# my_board3.net
KiCad netlist of a schematic drawn in EAGLE
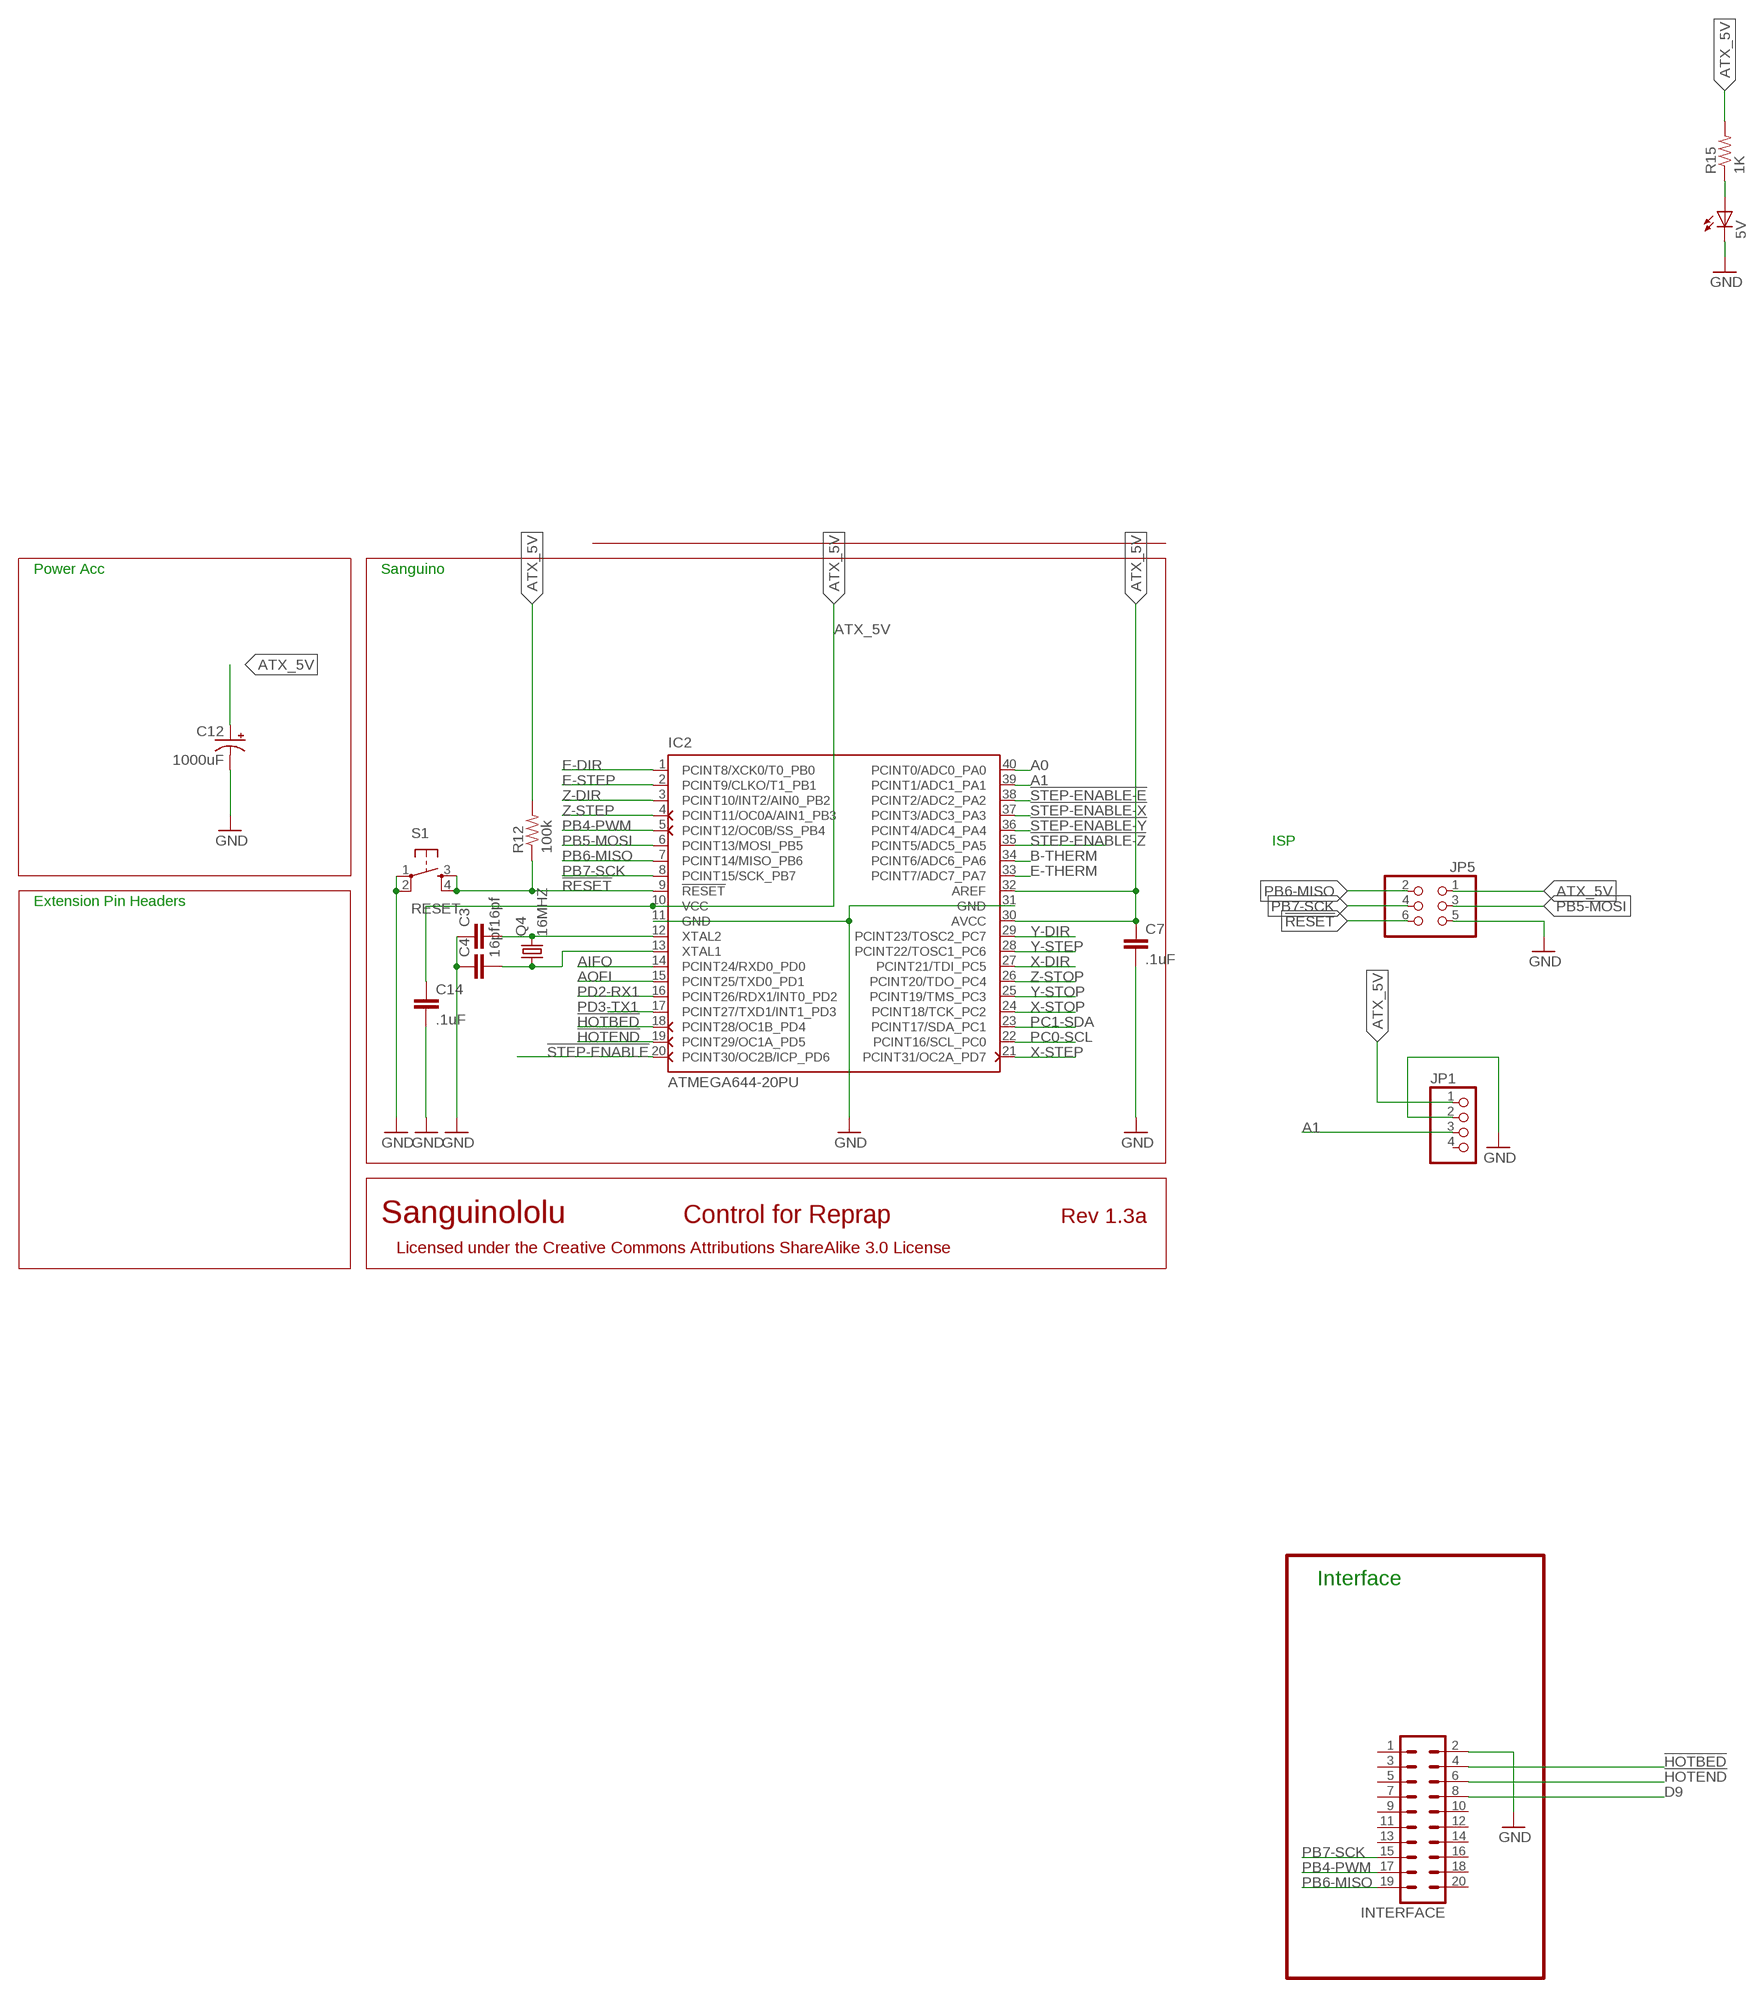
[diagram p0: schematic, sheet 1, part 1 of 2]
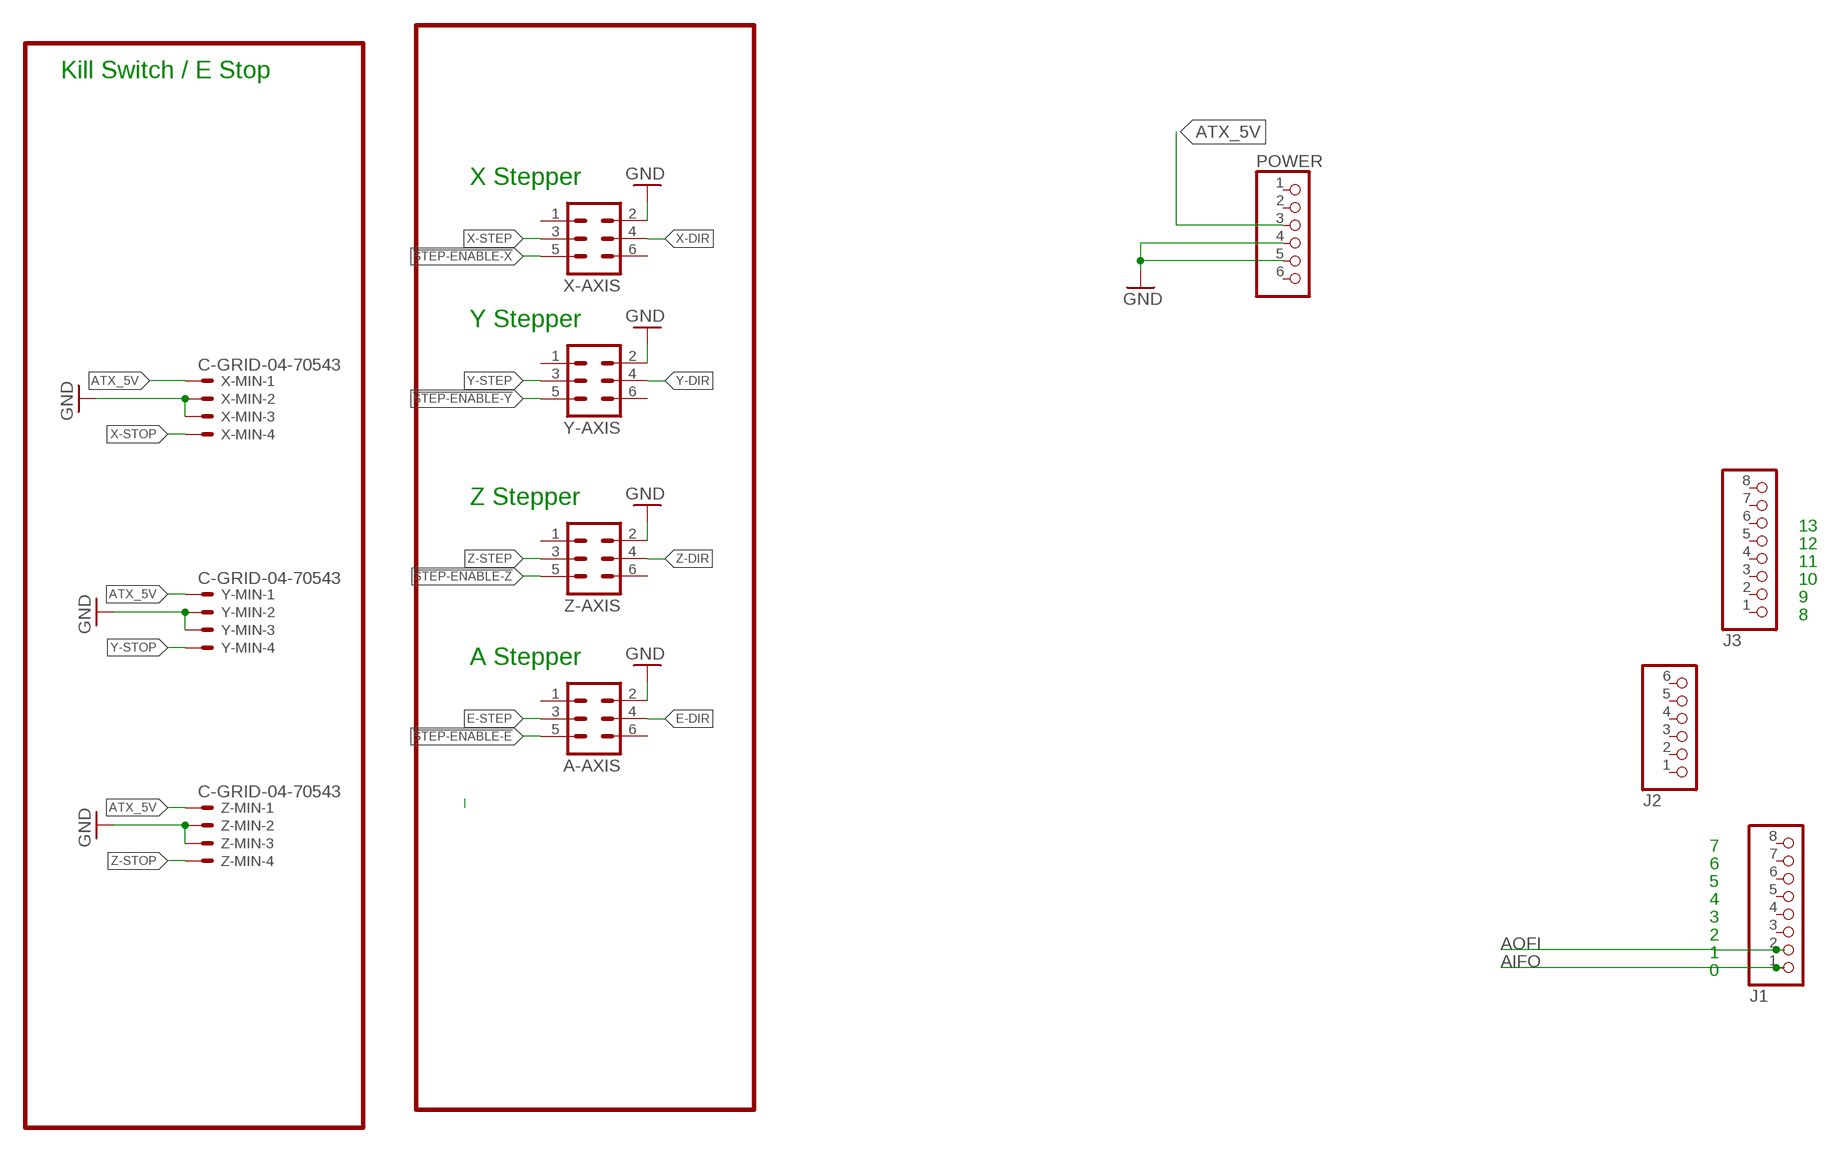
[diagram p1: schematic, sheet 1, part 2 of 2]

(export (version "E")
  (design (tool "Eeschema 10.0.6"))
  (components
    (comp (ref "5V")
      (value "LED0805")
      (footprint "eagle-import:LED-0805")
      (libsource (lib "eagle-import") (part "LED0805"))
    )
    (comp (ref "A-AXIS")
      (value "ML6")
      (footprint "eagle-import:ML6")
      (libsource (lib "eagle-import") (part "ML6"))
    )
    (comp (ref "C3")
      (value "16pf")
      (footprint "eagle-import:0805")
      (libsource (lib "eagle-import") (part "CAP0805"))
    )
    (comp (ref "C4")
      (value "16pf")
      (footprint "eagle-import:0805")
      (libsource (lib "eagle-import") (part "CAP0805"))
    )
    (comp (ref "C7")
      (value ".1uF")
      (footprint "eagle-import:0805")
      (libsource (lib "eagle-import") (part "CAP0805"))
    )
    (comp (ref "C12")
      (value "1000uF")
      (footprint "eagle-import:CPOL-RADIAL-1000UF-25V")
      (libsource (lib "eagle-import") (part "CAP_POLPTH4"))
    )
    (comp (ref "C14")
      (value ".1uF")
      (footprint "eagle-import:0805")
      (libsource (lib "eagle-import") (part "CAP0805"))
    )
    (comp (ref "IC2")
      (value "ATMEGA644-20PU")
      (footprint "eagle-import:DIL40")
      (libsource (lib "eagle-import") (part "ATMEGA644-PU20"))
    )
    (comp (ref "INTERFACE")
      (value "ML20")
      (footprint "eagle-import:ML20")
      (libsource (lib "eagle-import") (part "ML20"))
    )
    (comp (ref "J1")
      (value "PINHD-1X8")
      (footprint "eagle-import:1X08")
      (libsource (lib "eagle-import") (part "PINHD-1X8"))
    )
    (comp (ref "J2")
      (value "PINHD-1X6")
      (footprint "eagle-import:1X06")
      (libsource (lib "eagle-import") (part "PINHD-1X6"))
    )
    (comp (ref "J3")
      (value "PINHD-1X8")
      (footprint "eagle-import:1X08")
      (libsource (lib "eagle-import") (part "PINHD-1X8"))
    )
    (comp (ref "JP1")
      (value "PINHD-1X4")
      (footprint "eagle-import:1X04")
      (libsource (lib "eagle-import") (part "PINHD-1X4"))
    )
    (comp (ref "JP5")
      (value "PINHD-2X3")
      (footprint "eagle-import:2X03")
      (libsource (lib "eagle-import") (part "PINHD-2X3"))
    )
    (comp (ref "POWER")
      (value "PINHD-1X6")
      (footprint "eagle-import:1X06")
      (libsource (lib "eagle-import") (part "PINHD-1X6"))
    )
    (comp (ref "Q4")
      (value "16MHZ")
      (footprint "eagle-import:HC49_S")
      (libsource (lib "eagle-import") (part "CRYSTALHC49S"))
    )
    (comp (ref "R12")
      (value "100k")
      (footprint "eagle-import:AXIAL-0.3")
      (libsource (lib "eagle-import") (part "RESISTORPTH1"))
    )
    (comp (ref "R15")
      (value "1K")
      (footprint "eagle-import:0805")
      (libsource (lib "eagle-import") (part "RESISTOR"))
    )
    (comp (ref "S1")
      (value "RESET")
      (footprint "eagle-import:TACTILE-PTH")
      (libsource (lib "eagle-import") (part "TAC_SWITCHPTH"))
    )
    (comp (ref "X-AXIS")
      (value "ML6")
      (footprint "eagle-import:ML6")
      (libsource (lib "eagle-import") (part "ML6"))
    )
    (comp (ref "X-MIN")
      (value "C-GRID-04-70543")
      (footprint "eagle-import:70543-04")
      (libsource (lib "eagle-import") (part "C-GRID-04-70543"))
    )
    (comp (ref "Y-AXIS")
      (value "ML6")
      (footprint "eagle-import:ML6")
      (libsource (lib "eagle-import") (part "ML6"))
    )
    (comp (ref "Y-MIN")
      (value "C-GRID-04-70543")
      (footprint "eagle-import:70543-04")
      (libsource (lib "eagle-import") (part "C-GRID-04-70543"))
    )
    (comp (ref "Z-AXIS")
      (value "ML6")
      (footprint "eagle-import:ML6")
      (libsource (lib "eagle-import") (part "ML6"))
    )
    (comp (ref "Z-MIN")
      (value "C-GRID-04-70543")
      (footprint "eagle-import:70543-04")
      (libsource (lib "eagle-import") (part "C-GRID-04-70543"))
    )
  )
  (nets
    (net (code "1") (name "/A0") (class "Default")
      (node (ref "IC2") (pin "40") (pinfunction "PCINT0/ADC0_PA0_40") (pintype "bidirectional"))
    )
    (net (code "2") (name "/A1") (class "Default")
      (node (ref "IC2") (pin "39") (pinfunction "PCINT1/ADC1_PA1_39") (pintype "bidirectional"))
      (node (ref "JP1") (pin "3") (pinfunction "3_3") (pintype "passive"))
    )
    (net (code "3") (name "/AIFO") (class "Default")
      (node (ref "IC2") (pin "14") (pinfunction "PCINT24/RXD0_PD0_14") (pintype "bidirectional"))
      (node (ref "J1") (pin "1") (pinfunction "1_1") (pintype "passive"))
    )
    (net (code "4") (name "/AOFI") (class "Default")
      (node (ref "IC2") (pin "15") (pinfunction "PCINT25/TXD0_PD1_15") (pintype "bidirectional"))
      (node (ref "J1") (pin "2") (pinfunction "2_2") (pintype "passive"))
    )
    (net (code "5") (name "/B-THERM") (class "Default")
      (node (ref "IC2") (pin "34") (pinfunction "PCINT6/ADC6_PA6_34") (pintype "bidirectional"))
    )
    (net (code "6") (name "/D9") (class "Default")
      (node (ref "INTERFACE") (pin "8") (pinfunction "8_8") (pintype "passive"))
    )
    (net (code "7") (name "/E-THERM") (class "Default")
      (node (ref "IC2") (pin "33") (pinfunction "PCINT7/ADC7_PA7_33") (pintype "bidirectional"))
    )
    (net (code "8") (name "/PB4-PWM") (class "Default")
      (node (ref "IC2") (pin "5") (pinfunction "PCINT12/OC0B/SS_PB4_5") (pintype "bidirectional"))
      (node (ref "INTERFACE") (pin "17") (pinfunction "17_17") (pintype "passive"))
    )
    (net (code "9") (name "/PC0-SCL") (class "Default")
      (node (ref "IC2") (pin "22") (pinfunction "PCINT16/SCL_PC0_22") (pintype "bidirectional"))
    )
    (net (code "10") (name "/PC1-SDA") (class "Default")
      (node (ref "IC2") (pin "23") (pinfunction "PCINT17/SDA_PC1_23") (pintype "bidirectional"))
    )
    (net (code "11") (name "/PD2-RX1") (class "Default")
      (node (ref "IC2") (pin "16") (pinfunction "PCINT26/RDX1/INT0_PD2_16") (pintype "bidirectional"))
    )
    (net (code "12") (name "/PD3-TX1") (class "Default")
      (node (ref "IC2") (pin "17") (pinfunction "PCINT27/TXD1/INT1_PD3_17") (pintype "bidirectional"))
    )
    (net (code "13") (name "/~{HOTBED}") (class "Default")
      (node (ref "IC2") (pin "18") (pinfunction "PCINT28/OC1B_PD4_18") (pintype "bidirectional"))
      (node (ref "INTERFACE") (pin "4") (pinfunction "4_4") (pintype "passive"))
    )
    (net (code "14") (name "/~{HOTEND}") (class "Default")
      (node (ref "IC2") (pin "19") (pinfunction "PCINT29/OC1A_PD5_19") (pintype "bidirectional"))
      (node (ref "INTERFACE") (pin "6") (pinfunction "6_6") (pintype "passive"))
    )
    (net (code "15") (name "/~{RESET}") (class "Default")
      (node (ref "IC2") (pin "9") (pinfunction "~{RESET}_9") (pintype "input"))
      (node (ref "JP5") (pin "6") (pinfunction "6_6") (pintype "passive"))
      (node (ref "R12") (pin "P$1") (pinfunction "1_P$1") (pintype "passive"))
      (node (ref "S1") (pin "3") (pinfunction "3_3") (pintype "passive"))
      (node (ref "S1") (pin "4") (pinfunction "4_4") (pintype "passive"))
    )
    (net (code "16") (name "/~{STEP-ENABLE-E}") (class "Default")
      (node (ref "A-AXIS") (pin "5") (pinfunction "5_5") (pintype "passive"))
      (node (ref "IC2") (pin "38") (pinfunction "PCINT2/ADC2_PA2_38") (pintype "bidirectional"))
    )
    (net (code "17") (name "/~{STEP-ENABLE-X}") (class "Default")
      (node (ref "IC2") (pin "37") (pinfunction "PCINT3/ADC3_PA3_37") (pintype "bidirectional"))
      (node (ref "X-AXIS") (pin "5") (pinfunction "5_5") (pintype "passive"))
    )
    (net (code "18") (name "/~{STEP-ENABLE-Y}") (class "Default")
      (node (ref "IC2") (pin "36") (pinfunction "PCINT4/ADC4_PA4_36") (pintype "bidirectional"))
      (node (ref "Y-AXIS") (pin "5") (pinfunction "5_5") (pintype "passive"))
    )
    (net (code "19") (name "/~{STEP-ENABLE-Z}") (class "Default")
      (node (ref "IC2") (pin "35") (pinfunction "PCINT5/ADC5_PA5_35") (pintype "bidirectional"))
      (node (ref "Z-AXIS") (pin "5") (pinfunction "5_5") (pintype "passive"))
    )
    (net (code "20") (name "/~{STEP-ENABLE}") (class "Default")
      (node (ref "IC2") (pin "20") (pinfunction "PCINT30/OC2B/ICP_PD6_20") (pintype "bidirectional"))
    )
    (net (code "21") (name "ATX_5V") (class "Default")
      (node (ref "C12") (pin "1") (pinfunction "+_1") (pintype "passive"))
      (node (ref "C14") (pin "1") (pinfunction "1_1") (pintype "passive"))
      (node (ref "C7") (pin "1") (pinfunction "1_1") (pintype "passive"))
      (node (ref "IC2") (pin "10") (pinfunction "VCC_10") (pintype "power_in"))
      (node (ref "IC2") (pin "30") (pinfunction "AVCC_30") (pintype "power_in"))
      (node (ref "IC2") (pin "32") (pinfunction "AREF_32") (pintype "passive"))
      (node (ref "JP1") (pin "1") (pinfunction "1_1") (pintype "passive"))
      (node (ref "JP5") (pin "1") (pinfunction "1_1") (pintype "passive"))
      (node (ref "POWER") (pin "3") (pinfunction "3_3") (pintype "passive"))
      (node (ref "R12") (pin "P$2") (pinfunction "2_P$2") (pintype "passive"))
      (node (ref "R15") (pin "2") (pinfunction "2_2") (pintype "passive"))
      (node (ref "X-MIN") (pin "1") (pinfunction "S_1") (pintype "passive"))
      (node (ref "Y-MIN") (pin "1") (pinfunction "S_1") (pintype "passive"))
      (node (ref "Z-MIN") (pin "1") (pinfunction "S_1") (pintype "passive"))
    )
    (net (code "22") (name "E-DIR") (class "Default")
      (node (ref "A-AXIS") (pin "4") (pinfunction "4_4") (pintype "passive"))
      (node (ref "IC2") (pin "1") (pinfunction "PCINT8/XCK0/T0_PB0_1") (pintype "bidirectional"))
    )
    (net (code "23") (name "E-STEP") (class "Default")
      (node (ref "A-AXIS") (pin "3") (pinfunction "3_3") (pintype "passive"))
      (node (ref "IC2") (pin "2") (pinfunction "PCINT9/CLKO/T1_PB1_2") (pintype "bidirectional"))
    )
    (net (code "24") (name "GND") (class "Default")
      (node (ref "5V") (pin "C") (pinfunction "C_C") (pintype "passive"))
      (node (ref "A-AXIS") (pin "2") (pinfunction "2_2") (pintype "passive"))
      (node (ref "C12") (pin "2") (pinfunction "-_2") (pintype "passive"))
      (node (ref "C14") (pin "2") (pinfunction "2_2") (pintype "passive"))
      (node (ref "C3") (pin "1") (pinfunction "1_1") (pintype "passive"))
      (node (ref "C4") (pin "1") (pinfunction "1_1") (pintype "passive"))
      (node (ref "C7") (pin "2") (pinfunction "2_2") (pintype "passive"))
      (node (ref "IC2") (pin "11") (pinfunction "GND_11") (pintype "power_in"))
      (node (ref "IC2") (pin "31") (pinfunction "GND_31") (pintype "power_in"))
      (node (ref "INTERFACE") (pin "2") (pinfunction "2_2") (pintype "passive"))
      (node (ref "JP1") (pin "2") (pinfunction "2_2") (pintype "passive"))
      (node (ref "JP5") (pin "5") (pinfunction "5_5") (pintype "passive"))
      (node (ref "POWER") (pin "4") (pinfunction "4_4") (pintype "passive"))
      (node (ref "POWER") (pin "5") (pinfunction "5_5") (pintype "passive"))
      (node (ref "S1") (pin "1") (pinfunction "1_1") (pintype "passive"))
      (node (ref "S1") (pin "2") (pinfunction "2_2") (pintype "passive"))
      (node (ref "X-AXIS") (pin "2") (pinfunction "2_2") (pintype "passive"))
      (node (ref "X-MIN") (pin "2") (pinfunction "S_2") (pintype "passive"))
      (node (ref "X-MIN") (pin "3") (pinfunction "S_3") (pintype "passive"))
      (node (ref "Y-AXIS") (pin "2") (pinfunction "2_2") (pintype "passive"))
      (node (ref "Y-MIN") (pin "2") (pinfunction "S_2") (pintype "passive"))
      (node (ref "Y-MIN") (pin "3") (pinfunction "S_3") (pintype "passive"))
      (node (ref "Z-AXIS") (pin "2") (pinfunction "2_2") (pintype "passive"))
      (node (ref "Z-MIN") (pin "2") (pinfunction "S_2") (pintype "passive"))
      (node (ref "Z-MIN") (pin "3") (pinfunction "S_3") (pintype "passive"))
    )
    (net (code "25") (name "Net-(5V-PadA)") (class "Default")
      (node (ref "5V") (pin "A") (pinfunction "A_A") (pintype "passive"))
      (node (ref "R15") (pin "1") (pinfunction "1_1") (pintype "passive"))
    )
    (net (code "26") (name "Net-(IC2-XTAL1)") (class "Default")
      (node (ref "C4") (pin "2") (pinfunction "2_2") (pintype "passive"))
      (node (ref "IC2") (pin "13") (pinfunction "XTAL1_13") (pintype "input"))
      (node (ref "Q4") (pin "1") (pinfunction "1_1") (pintype "passive"))
    )
    (net (code "27") (name "Net-(IC2-XTAL2)") (class "Default")
      (node (ref "C3") (pin "2") (pinfunction "2_2") (pintype "passive"))
      (node (ref "IC2") (pin "12") (pinfunction "XTAL2_12") (pintype "output"))
      (node (ref "Q4") (pin "2") (pinfunction "2_2") (pintype "passive"))
    )
    (net (code "28") (name "PB5-MOSI") (class "Default")
      (node (ref "IC2") (pin "6") (pinfunction "PCINT13/MOSI_PB5_6") (pintype "bidirectional"))
      (node (ref "JP5") (pin "3") (pinfunction "3_3") (pintype "passive"))
    )
    (net (code "29") (name "PB6-MISO") (class "Default")
      (node (ref "IC2") (pin "7") (pinfunction "PCINT14/MISO_PB6_7") (pintype "bidirectional"))
      (node (ref "INTERFACE") (pin "19") (pinfunction "19_19") (pintype "passive"))
      (node (ref "JP5") (pin "2") (pinfunction "2_2") (pintype "passive"))
    )
    (net (code "30") (name "PB7-SCK") (class "Default")
      (node (ref "IC2") (pin "8") (pinfunction "PCINT15/SCK_PB7_8") (pintype "bidirectional"))
      (node (ref "INTERFACE") (pin "15") (pinfunction "15_15") (pintype "passive"))
      (node (ref "JP5") (pin "4") (pinfunction "4_4") (pintype "passive"))
    )
    (net (code "31") (name "X-DIR") (class "Default")
      (node (ref "IC2") (pin "27") (pinfunction "PCINT21/TDI_PC5_27") (pintype "bidirectional"))
      (node (ref "X-AXIS") (pin "4") (pinfunction "4_4") (pintype "passive"))
    )
    (net (code "32") (name "X-STEP") (class "Default")
      (node (ref "IC2") (pin "21") (pinfunction "PCINT31/OC2A_PD7_21") (pintype "bidirectional"))
      (node (ref "X-AXIS") (pin "3") (pinfunction "3_3") (pintype "passive"))
    )
    (net (code "33") (name "X-STOP") (class "Default")
      (node (ref "IC2") (pin "24") (pinfunction "PCINT18/TCK_PC2_24") (pintype "bidirectional"))
      (node (ref "X-MIN") (pin "4") (pinfunction "S_4") (pintype "passive"))
    )
    (net (code "34") (name "Y-DIR") (class "Default")
      (node (ref "IC2") (pin "29") (pinfunction "PCINT23/TOSC2_PC7_29") (pintype "bidirectional"))
      (node (ref "Y-AXIS") (pin "4") (pinfunction "4_4") (pintype "passive"))
    )
    (net (code "35") (name "Y-STEP") (class "Default")
      (node (ref "IC2") (pin "28") (pinfunction "PCINT22/TOSC1_PC6_28") (pintype "bidirectional"))
      (node (ref "Y-AXIS") (pin "3") (pinfunction "3_3") (pintype "passive"))
    )
    (net (code "36") (name "Y-STOP") (class "Default")
      (node (ref "IC2") (pin "25") (pinfunction "PCINT19/TMS_PC3_25") (pintype "bidirectional"))
      (node (ref "Y-MIN") (pin "4") (pinfunction "S_4") (pintype "passive"))
    )
    (net (code "37") (name "Z-DIR") (class "Default")
      (node (ref "IC2") (pin "3") (pinfunction "PCINT10/INT2/AIN0_PB2_3") (pintype "bidirectional"))
      (node (ref "Z-AXIS") (pin "4") (pinfunction "4_4") (pintype "passive"))
    )
    (net (code "38") (name "Z-STEP") (class "Default")
      (node (ref "IC2") (pin "4") (pinfunction "PCINT11/OC0A/AIN1_PB3_4") (pintype "bidirectional"))
      (node (ref "Z-AXIS") (pin "3") (pinfunction "3_3") (pintype "passive"))
    )
    (net (code "39") (name "Z-STOP") (class "Default")
      (node (ref "IC2") (pin "26") (pinfunction "PCINT20/TDO_PC4_26") (pintype "bidirectional"))
      (node (ref "Z-MIN") (pin "4") (pinfunction "S_4") (pintype "passive"))
    )
    (net (code "40") (name "unconnected-(A-AXIS-Pad1)") (class "Default")
      (node (ref "A-AXIS") (pin "1") (pinfunction "1_1") (pintype "passive"))
    )
    (net (code "41") (name "unconnected-(A-AXIS-Pad6)") (class "Default")
      (node (ref "A-AXIS") (pin "6") (pinfunction "6_6") (pintype "passive"))
    )
    (net (code "42") (name "unconnected-(INTERFACE-Pad1)") (class "Default")
      (node (ref "INTERFACE") (pin "1") (pinfunction "1_1") (pintype "passive"))
    )
    (net (code "43") (name "unconnected-(INTERFACE-Pad3)") (class "Default")
      (node (ref "INTERFACE") (pin "3") (pinfunction "3_3") (pintype "passive"))
    )
    (net (code "44") (name "unconnected-(INTERFACE-Pad5)") (class "Default")
      (node (ref "INTERFACE") (pin "5") (pinfunction "5_5") (pintype "passive"))
    )
    (net (code "45") (name "unconnected-(INTERFACE-Pad7)") (class "Default")
      (node (ref "INTERFACE") (pin "7") (pinfunction "7_7") (pintype "passive"))
    )
    (net (code "46") (name "unconnected-(INTERFACE-Pad9)") (class "Default")
      (node (ref "INTERFACE") (pin "9") (pinfunction "9_9") (pintype "passive"))
    )
    (net (code "47") (name "unconnected-(INTERFACE-Pad10)") (class "Default")
      (node (ref "INTERFACE") (pin "10") (pinfunction "10_10") (pintype "passive"))
    )
    (net (code "48") (name "unconnected-(INTERFACE-Pad11)") (class "Default")
      (node (ref "INTERFACE") (pin "11") (pinfunction "11_11") (pintype "passive"))
    )
    (net (code "49") (name "unconnected-(INTERFACE-Pad12)") (class "Default")
      (node (ref "INTERFACE") (pin "12") (pinfunction "12_12") (pintype "passive"))
    )
    (net (code "50") (name "unconnected-(INTERFACE-Pad13)") (class "Default")
      (node (ref "INTERFACE") (pin "13") (pinfunction "13_13") (pintype "passive"))
    )
    (net (code "51") (name "unconnected-(INTERFACE-Pad14)") (class "Default")
      (node (ref "INTERFACE") (pin "14") (pinfunction "14_14") (pintype "passive"))
    )
    (net (code "52") (name "unconnected-(INTERFACE-Pad16)") (class "Default")
      (node (ref "INTERFACE") (pin "16") (pinfunction "16_16") (pintype "passive"))
    )
    (net (code "53") (name "unconnected-(INTERFACE-Pad18)") (class "Default")
      (node (ref "INTERFACE") (pin "18") (pinfunction "18_18") (pintype "passive"))
    )
    (net (code "54") (name "unconnected-(INTERFACE-Pad20)") (class "Default")
      (node (ref "INTERFACE") (pin "20") (pinfunction "20_20") (pintype "passive"))
    )
    (net (code "55") (name "unconnected-(J1-Pad3)") (class "Default")
      (node (ref "J1") (pin "3") (pinfunction "3_3") (pintype "passive"))
    )
    (net (code "56") (name "unconnected-(J1-Pad4)") (class "Default")
      (node (ref "J1") (pin "4") (pinfunction "4_4") (pintype "passive"))
    )
    (net (code "57") (name "unconnected-(J1-Pad5)") (class "Default")
      (node (ref "J1") (pin "5") (pinfunction "5_5") (pintype "passive"))
    )
    (net (code "58") (name "unconnected-(J1-Pad6)") (class "Default")
      (node (ref "J1") (pin "6") (pinfunction "6_6") (pintype "passive"))
    )
    (net (code "59") (name "unconnected-(J1-Pad7)") (class "Default")
      (node (ref "J1") (pin "7") (pinfunction "7_7") (pintype "passive"))
    )
    (net (code "60") (name "unconnected-(J1-Pad8)") (class "Default")
      (node (ref "J1") (pin "8") (pinfunction "8_8") (pintype "passive"))
    )
    (net (code "61") (name "unconnected-(J2-Pad1)") (class "Default")
      (node (ref "J2") (pin "1") (pinfunction "1_1") (pintype "passive"))
    )
    (net (code "62") (name "unconnected-(J2-Pad2)") (class "Default")
      (node (ref "J2") (pin "2") (pinfunction "2_2") (pintype "passive"))
    )
    (net (code "63") (name "unconnected-(J2-Pad3)") (class "Default")
      (node (ref "J2") (pin "3") (pinfunction "3_3") (pintype "passive"))
    )
    (net (code "64") (name "unconnected-(J2-Pad4)") (class "Default")
      (node (ref "J2") (pin "4") (pinfunction "4_4") (pintype "passive"))
    )
    (net (code "65") (name "unconnected-(J2-Pad5)") (class "Default")
      (node (ref "J2") (pin "5") (pinfunction "5_5") (pintype "passive"))
    )
    (net (code "66") (name "unconnected-(J2-Pad6)") (class "Default")
      (node (ref "J2") (pin "6") (pinfunction "6_6") (pintype "passive"))
    )
    (net (code "67") (name "unconnected-(J3-Pad1)") (class "Default")
      (node (ref "J3") (pin "1") (pinfunction "1_1") (pintype "passive"))
    )
    (net (code "68") (name "unconnected-(J3-Pad2)") (class "Default")
      (node (ref "J3") (pin "2") (pinfunction "2_2") (pintype "passive"))
    )
    (net (code "69") (name "unconnected-(J3-Pad3)") (class "Default")
      (node (ref "J3") (pin "3") (pinfunction "3_3") (pintype "passive"))
    )
    (net (code "70") (name "unconnected-(J3-Pad4)") (class "Default")
      (node (ref "J3") (pin "4") (pinfunction "4_4") (pintype "passive"))
    )
    (net (code "71") (name "unconnected-(J3-Pad5)") (class "Default")
      (node (ref "J3") (pin "5") (pinfunction "5_5") (pintype "passive"))
    )
    (net (code "72") (name "unconnected-(J3-Pad6)") (class "Default")
      (node (ref "J3") (pin "6") (pinfunction "6_6") (pintype "passive"))
    )
    (net (code "73") (name "unconnected-(J3-Pad7)") (class "Default")
      (node (ref "J3") (pin "7") (pinfunction "7_7") (pintype "passive"))
    )
    (net (code "74") (name "unconnected-(J3-Pad8)") (class "Default")
      (node (ref "J3") (pin "8") (pinfunction "8_8") (pintype "passive"))
    )
    (net (code "75") (name "unconnected-(JP1-Pad4)") (class "Default")
      (node (ref "JP1") (pin "4") (pinfunction "4_4") (pintype "passive"))
    )
    (net (code "76") (name "unconnected-(POWER-Pad1)") (class "Default")
      (node (ref "POWER") (pin "1") (pinfunction "1_1") (pintype "passive"))
    )
    (net (code "77") (name "unconnected-(POWER-Pad2)") (class "Default")
      (node (ref "POWER") (pin "2") (pinfunction "2_2") (pintype "passive"))
    )
    (net (code "78") (name "unconnected-(POWER-Pad6)") (class "Default")
      (node (ref "POWER") (pin "6") (pinfunction "6_6") (pintype "passive"))
    )
    (net (code "79") (name "unconnected-(X-AXIS-Pad1)") (class "Default")
      (node (ref "X-AXIS") (pin "1") (pinfunction "1_1") (pintype "passive"))
    )
    (net (code "80") (name "unconnected-(X-AXIS-Pad6)") (class "Default")
      (node (ref "X-AXIS") (pin "6") (pinfunction "6_6") (pintype "passive"))
    )
    (net (code "81") (name "unconnected-(Y-AXIS-Pad1)") (class "Default")
      (node (ref "Y-AXIS") (pin "1") (pinfunction "1_1") (pintype "passive"))
    )
    (net (code "82") (name "unconnected-(Y-AXIS-Pad6)") (class "Default")
      (node (ref "Y-AXIS") (pin "6") (pinfunction "6_6") (pintype "passive"))
    )
    (net (code "83") (name "unconnected-(Z-AXIS-Pad1)") (class "Default")
      (node (ref "Z-AXIS") (pin "1") (pinfunction "1_1") (pintype "passive"))
    )
    (net (code "84") (name "unconnected-(Z-AXIS-Pad6)") (class "Default")
      (node (ref "Z-AXIS") (pin "6") (pinfunction "6_6") (pintype "passive"))
    )
  )
)
